# ce2_redraw.net
KiCad netlist of a schematic drawn in EAGLE
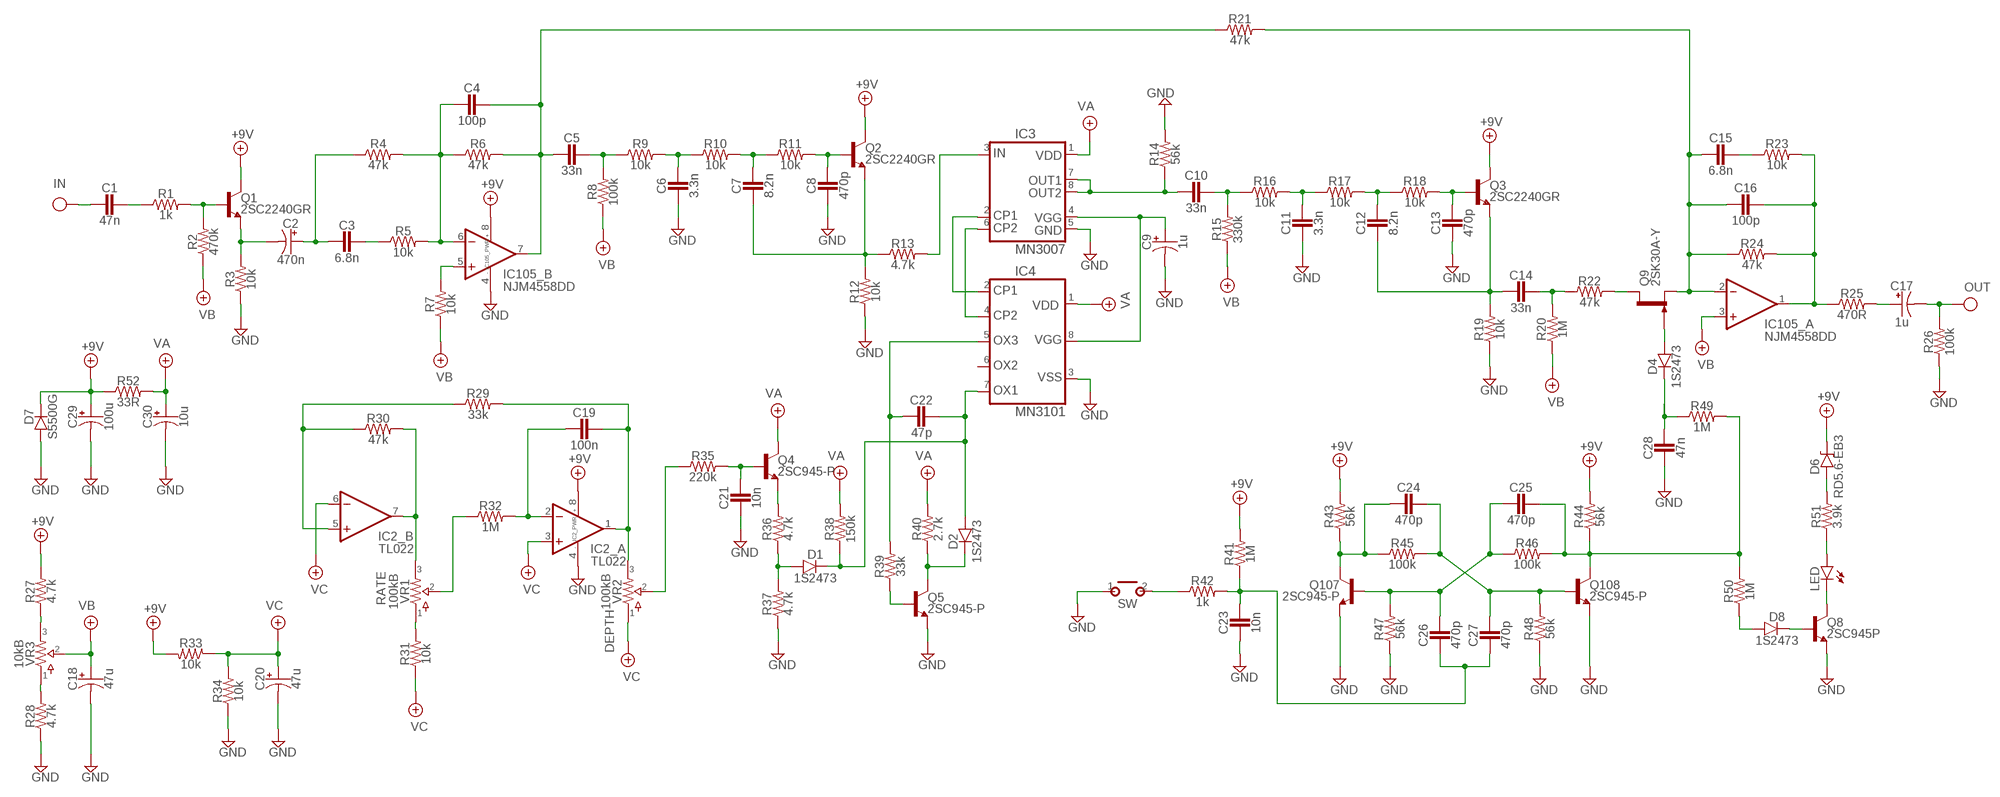
[diagram p0: schematic, sheet 1]

(export (version "E")
  (design (tool "Eeschema 10.0.6"))
  (components
    (comp (ref "C1")
      (value "47n")
      (footprint "eagle-import:BOX_SMALL")
      (libsource (lib "eagle-import") (part "CER/FILMBOX.1"))
    )
    (comp (ref "C2")
      (value "470n")
      (footprint "eagle-import:040_020")
      (libsource (lib "eagle-import") (part "0400"))
    )
    (comp (ref "C3")
      (value "6.8n")
      (footprint "eagle-import:BOX_SMALL")
      (libsource (lib "eagle-import") (part "CER/FILMBOX.1"))
    )
    (comp (ref "C4")
      (value "100p")
      (footprint "eagle-import:BOX_SMALL")
      (libsource (lib "eagle-import") (part "CER/FILMBOX.1"))
    )
    (comp (ref "C5")
      (value "33n")
      (footprint "eagle-import:BOX_SMALL")
      (libsource (lib "eagle-import") (part "CER/FILMBOX.1"))
    )
    (comp (ref "C6")
      (value "3.3n")
      (footprint "eagle-import:BOX_SMALL")
      (libsource (lib "eagle-import") (part "CER/FILMBOX.1"))
    )
    (comp (ref "C7")
      (value "8.2n")
      (footprint "eagle-import:BOX_SMALL")
      (libsource (lib "eagle-import") (part "CER/FILMBOX.1"))
    )
    (comp (ref "C8")
      (value "470p")
      (footprint "eagle-import:BOX_SMALL")
      (libsource (lib "eagle-import") (part "CER/FILMBOX.1"))
    )
    (comp (ref "C9")
      (value "1u")
      (footprint "eagle-import:040_020")
      (libsource (lib "eagle-import") (part "0400"))
    )
    (comp (ref "C10")
      (value "33n")
      (footprint "eagle-import:BOX_SMALL")
      (libsource (lib "eagle-import") (part "CER/FILMBOX.1"))
    )
    (comp (ref "C11")
      (value "3.3n")
      (footprint "eagle-import:BOX_SMALL")
      (libsource (lib "eagle-import") (part "CER/FILMBOX.1"))
    )
    (comp (ref "C12")
      (value "8.2n")
      (footprint "eagle-import:BOX_SMALL")
      (libsource (lib "eagle-import") (part "CER/FILMBOX.1"))
    )
    (comp (ref "C13")
      (value "470p")
      (footprint "eagle-import:BOX_SMALL")
      (libsource (lib "eagle-import") (part "CER/FILMBOX.1"))
    )
    (comp (ref "C14")
      (value "33n")
      (footprint "eagle-import:BOX_SMALL")
      (libsource (lib "eagle-import") (part "CER/FILMBOX.1"))
    )
    (comp (ref "C15")
      (value "6.8n")
      (footprint "eagle-import:BOX_SMALL")
      (libsource (lib "eagle-import") (part "CER/FILMBOX.1"))
    )
    (comp (ref "C16")
      (value "100p")
      (footprint "eagle-import:BOX_SMALL")
      (libsource (lib "eagle-import") (part "CER/FILMBOX.1"))
    )
    (comp (ref "C17")
      (value "1u")
      (footprint "eagle-import:040_020")
      (libsource (lib "eagle-import") (part "0400"))
    )
    (comp (ref "C18")
      (value "47u")
      (footprint "eagle-import:040_020")
      (libsource (lib "eagle-import") (part "0400"))
    )
    (comp (ref "C19")
      (value "100n")
      (footprint "eagle-import:BOX_SMALL")
      (libsource (lib "eagle-import") (part "CER/FILMBOX.1"))
    )
    (comp (ref "C20")
      (value "47u")
      (footprint "eagle-import:040_020")
      (libsource (lib "eagle-import") (part "0400"))
    )
    (comp (ref "C21")
      (value "10n")
      (footprint "eagle-import:BOX_SMALL")
      (libsource (lib "eagle-import") (part "CER/FILMBOX.1"))
    )
    (comp (ref "C22")
      (value "47p")
      (footprint "eagle-import:BOX_SMALL")
      (libsource (lib "eagle-import") (part "CER/FILMBOX.1"))
    )
    (comp (ref "C23")
      (value "10n")
      (footprint "eagle-import:BOX_SMALL")
      (libsource (lib "eagle-import") (part "CER/FILMBOX.1"))
    )
    (comp (ref "C24")
      (value "470p")
      (footprint "eagle-import:BOX_SMALL")
      (libsource (lib "eagle-import") (part "CER/FILMBOX.1"))
    )
    (comp (ref "C25")
      (value "470p")
      (footprint "eagle-import:BOX_SMALL")
      (libsource (lib "eagle-import") (part "CER/FILMBOX.1"))
    )
    (comp (ref "C26")
      (value "470p")
      (footprint "eagle-import:BOX_SMALL")
      (libsource (lib "eagle-import") (part "CER/FILMBOX.1"))
    )
    (comp (ref "C27")
      (value "470p")
      (footprint "eagle-import:BOX_SMALL")
      (libsource (lib "eagle-import") (part "CER/FILMBOX.1"))
    )
    (comp (ref "C28")
      (value "47n")
      (footprint "eagle-import:BOX_SMALL")
      (libsource (lib "eagle-import") (part "CER/FILMBOX.1"))
    )
    (comp (ref "C29")
      (value "100u")
      (footprint "eagle-import:040_020")
      (libsource (lib "eagle-import") (part "0400"))
    )
    (comp (ref "C30")
      (value "10u")
      (footprint "eagle-import:040_020")
      (libsource (lib "eagle-import") (part "0400"))
    )
    (comp (ref "D1")
      (value "1S2473")
      (footprint "eagle-import:DO35-2")
      (libsource (lib "eagle-import") (part "DO35.2"))
    )
    (comp (ref "D2")
      (value "1S2473")
      (footprint "eagle-import:DO35-2")
      (libsource (lib "eagle-import") (part "DO35.2"))
    )
    (comp (ref "D4")
      (value "1S2473")
      (footprint "eagle-import:DO35-2")
      (libsource (lib "eagle-import") (part "DO35.2"))
    )
    (comp (ref "D6")
      (value "RD5.6-EB3")
      (footprint "eagle-import:DO41-1")
      (libsource (lib "eagle-import") (part "ZENER.1"))
    )
    (comp (ref "D7")
      (value "S5500G")
      (footprint "eagle-import:DO35-2")
      (libsource (lib "eagle-import") (part "DO35.2"))
    )
    (comp (ref "D8")
      (value "1S2473")
      (footprint "eagle-import:DO35-2")
      (libsource (lib "eagle-import") (part "DO35.2"))
    )
    (comp (ref "IC2")
      (value "TL022")
      (footprint "eagle-import:DIL0")
      (libsource (lib "eagle-import") (part "DUALTH"))
    )
    (comp (ref "IC3")
      (value "MN3007")
      (footprint "eagle-import:DIL0")
      (libsource (lib "eagle-import") (part "BL3208"))
    )
    (comp (ref "IC4")
      (value "MN3101")
      (footprint "eagle-import:DIL8")
      (libsource (lib "eagle-import") (part "CLOCK"))
    )
    (comp (ref "IC105")
      (value "NJM4558DD")
      (footprint "eagle-import:DIL0")
      (libsource (lib "eagle-import") (part "DUALTH"))
    )
    (comp (ref "LED")
      (value "LED")
      (footprint "eagle-import:3MM_D")
      (libsource (lib "eagle-import") (part "LED"))
    )
    (comp (ref "Q1")
      (value "2SC2240GR")
      (footprint "eagle-import:TO92-")
      (libsource (lib "eagle-import") (part "2SC828A"))
    )
    (comp (ref "Q2")
      (value "2SC2240GR")
      (footprint "eagle-import:TO92-")
      (libsource (lib "eagle-import") (part "2SC828A"))
    )
    (comp (ref "Q3")
      (value "2SC2240GR")
      (footprint "eagle-import:TO92-")
      (libsource (lib "eagle-import") (part "2SC828A"))
    )
    (comp (ref "Q4")
      (value "2SC945-P")
      (footprint "eagle-import:TO92-")
      (libsource (lib "eagle-import") (part "2SC828A"))
    )
    (comp (ref "Q5")
      (value "2SC945-P")
      (footprint "eagle-import:TO92-")
      (libsource (lib "eagle-import") (part "2SC828A"))
    )
    (comp (ref "Q8")
      (value "2SC945P")
      (footprint "eagle-import:TO92-")
      (libsource (lib "eagle-import") (part "2SC828A"))
    )
    (comp (ref "Q9")
      (value "2SK30A-Y")
      (footprint "eagle-import:TO92-")
      (libsource (lib "eagle-import") (part "2N5457"))
    )
    (comp (ref "Q107")
      (value "2SC945-P")
      (footprint "eagle-import:TO92-")
      (libsource (lib "eagle-import") (part "2SC828A"))
    )
    (comp (ref "Q108")
      (value "2SC945-P")
      (footprint "eagle-import:TO92-")
      (libsource (lib "eagle-import") (part "2SC828A"))
    )
    (comp (ref "R1")
      (value "1k")
      (footprint "eagle-import:R0207_3")
      (libsource (lib "eagle-import") (part "R_.3B"))
    )
    (comp (ref "R2")
      (value "470k")
      (footprint "eagle-import:R0207_3")
      (libsource (lib "eagle-import") (part "R_.3B"))
    )
    (comp (ref "R3")
      (value "10k")
      (footprint "eagle-import:R0207_3")
      (libsource (lib "eagle-import") (part "R_.3B"))
    )
    (comp (ref "R4")
      (value "47k")
      (footprint "eagle-import:R0207_3")
      (libsource (lib "eagle-import") (part "R_.3B"))
    )
    (comp (ref "R5")
      (value "10k")
      (footprint "eagle-import:R0207_3")
      (libsource (lib "eagle-import") (part "R_.3B"))
    )
    (comp (ref "R6")
      (value "47k")
      (footprint "eagle-import:R0207_3")
      (libsource (lib "eagle-import") (part "R_.3B"))
    )
    (comp (ref "R7")
      (value "10k")
      (footprint "eagle-import:R0207_3")
      (libsource (lib "eagle-import") (part "R_.3B"))
    )
    (comp (ref "R8")
      (value "100k")
      (footprint "eagle-import:R0207_3")
      (libsource (lib "eagle-import") (part "R_.3B"))
    )
    (comp (ref "R9")
      (value "10k")
      (footprint "eagle-import:R0207_3")
      (libsource (lib "eagle-import") (part "R_.3B"))
    )
    (comp (ref "R10")
      (value "10k")
      (footprint "eagle-import:R0207_3")
      (libsource (lib "eagle-import") (part "R_.3B"))
    )
    (comp (ref "R11")
      (value "10k")
      (footprint "eagle-import:R0207_3")
      (libsource (lib "eagle-import") (part "R_.3B"))
    )
    (comp (ref "R12")
      (value "10k")
      (footprint "eagle-import:R0207_3")
      (libsource (lib "eagle-import") (part "R_.3B"))
    )
    (comp (ref "R13")
      (value "4.7k")
      (footprint "eagle-import:R0207_3")
      (libsource (lib "eagle-import") (part "R_.3B"))
    )
    (comp (ref "R14")
      (value "56k")
      (footprint "eagle-import:R0207_3")
      (libsource (lib "eagle-import") (part "R_.3B"))
    )
    (comp (ref "R15")
      (value "330k")
      (footprint "eagle-import:R0207_3")
      (libsource (lib "eagle-import") (part "R_.3B"))
    )
    (comp (ref "R16")
      (value "10k")
      (footprint "eagle-import:R0207_3")
      (libsource (lib "eagle-import") (part "R_.3B"))
    )
    (comp (ref "R17")
      (value "10k")
      (footprint "eagle-import:R0207_3")
      (libsource (lib "eagle-import") (part "R_.3B"))
    )
    (comp (ref "R18")
      (value "10k")
      (footprint "eagle-import:R0207_3")
      (libsource (lib "eagle-import") (part "R_.3B"))
    )
    (comp (ref "R19")
      (value "10k")
      (footprint "eagle-import:R0207_3")
      (libsource (lib "eagle-import") (part "R_.3B"))
    )
    (comp (ref "R20")
      (value "1M")
      (footprint "eagle-import:R0207_3")
      (libsource (lib "eagle-import") (part "R_.3B"))
    )
    (comp (ref "R21")
      (value "47k")
      (footprint "eagle-import:R0207_3")
      (libsource (lib "eagle-import") (part "R_.3B"))
    )
    (comp (ref "R22")
      (value "47k")
      (footprint "eagle-import:R0207_3")
      (libsource (lib "eagle-import") (part "R_.3B"))
    )
    (comp (ref "R23")
      (value "10k")
      (footprint "eagle-import:R0207_3")
      (libsource (lib "eagle-import") (part "R_.3B"))
    )
    (comp (ref "R24")
      (value "47k")
      (footprint "eagle-import:R0207_3")
      (libsource (lib "eagle-import") (part "R_.3B"))
    )
    (comp (ref "R25")
      (value "470R")
      (footprint "eagle-import:R0207_3")
      (libsource (lib "eagle-import") (part "R_.3B"))
    )
    (comp (ref "R26")
      (value "100k")
      (footprint "eagle-import:R0207_3")
      (libsource (lib "eagle-import") (part "R_.3B"))
    )
    (comp (ref "R27")
      (value "4.7k")
      (footprint "eagle-import:R0207_3")
      (libsource (lib "eagle-import") (part "R_.3B"))
    )
    (comp (ref "R28")
      (value "4.7k")
      (footprint "eagle-import:R0207_3")
      (libsource (lib "eagle-import") (part "R_.3B"))
    )
    (comp (ref "R29")
      (value "33k")
      (footprint "eagle-import:R0207_3")
      (libsource (lib "eagle-import") (part "R_.3B"))
    )
    (comp (ref "R30")
      (value "47k")
      (footprint "eagle-import:R0207_3")
      (libsource (lib "eagle-import") (part "R_.3B"))
    )
    (comp (ref "R31")
      (value "10k")
      (footprint "eagle-import:R0207_3")
      (libsource (lib "eagle-import") (part "R_.3B"))
    )
    (comp (ref "R32")
      (value "1M")
      (footprint "eagle-import:R0207_3")
      (libsource (lib "eagle-import") (part "R_.3B"))
    )
    (comp (ref "R33")
      (value "10k")
      (footprint "eagle-import:R0207_3")
      (libsource (lib "eagle-import") (part "R_.3B"))
    )
    (comp (ref "R34")
      (value "10k")
      (footprint "eagle-import:R0207_3")
      (libsource (lib "eagle-import") (part "R_.3B"))
    )
    (comp (ref "R35")
      (value "220k")
      (footprint "eagle-import:R0207_3")
      (libsource (lib "eagle-import") (part "R_.3B"))
    )
    (comp (ref "R36")
      (value "4.7k")
      (footprint "eagle-import:R0207_3")
      (libsource (lib "eagle-import") (part "R_.3B"))
    )
    (comp (ref "R37")
      (value "4.7k")
      (footprint "eagle-import:R0207_3")
      (libsource (lib "eagle-import") (part "R_.3B"))
    )
    (comp (ref "R38")
      (value "150k")
      (footprint "eagle-import:R0207_3")
      (libsource (lib "eagle-import") (part "R_.3B"))
    )
    (comp (ref "R39")
      (value "33k")
      (footprint "eagle-import:R0207_3")
      (libsource (lib "eagle-import") (part "R_.3B"))
    )
    (comp (ref "R40")
      (value "2.7k")
      (footprint "eagle-import:R0207_3")
      (libsource (lib "eagle-import") (part "R_.3B"))
    )
    (comp (ref "R41")
      (value "1M")
      (footprint "eagle-import:R0207_3")
      (libsource (lib "eagle-import") (part "R_.3B"))
    )
    (comp (ref "R42")
      (value "1k")
      (footprint "eagle-import:R0207_3")
      (libsource (lib "eagle-import") (part "R_.3B"))
    )
    (comp (ref "R43")
      (value "56k")
      (footprint "eagle-import:R0207_3")
      (libsource (lib "eagle-import") (part "R_.3B"))
    )
    (comp (ref "R44")
      (value "56k")
      (footprint "eagle-import:R0207_3")
      (libsource (lib "eagle-import") (part "R_.3B"))
    )
    (comp (ref "R45")
      (value "100k")
      (footprint "eagle-import:R0207_3")
      (libsource (lib "eagle-import") (part "R_.3B"))
    )
    (comp (ref "R46")
      (value "100k")
      (footprint "eagle-import:R0207_3")
      (libsource (lib "eagle-import") (part "R_.3B"))
    )
    (comp (ref "R47")
      (value "56k")
      (footprint "eagle-import:R0207_3")
      (libsource (lib "eagle-import") (part "R_.3B"))
    )
    (comp (ref "R48")
      (value "56k")
      (footprint "eagle-import:R0207_3")
      (libsource (lib "eagle-import") (part "R_.3B"))
    )
    (comp (ref "R49")
      (value "1M")
      (footprint "eagle-import:R0207_3")
      (libsource (lib "eagle-import") (part "R_.3B"))
    )
    (comp (ref "R50")
      (value "1M")
      (footprint "eagle-import:R0207_3")
      (libsource (lib "eagle-import") (part "R_.3B"))
    )
    (comp (ref "R51")
      (value "3.9k")
      (footprint "eagle-import:R0207_3")
      (libsource (lib "eagle-import") (part "R_.3B"))
    )
    (comp (ref "R52")
      (value "33R")
      (footprint "eagle-import:R0207_3")
      (libsource (lib "eagle-import") (part "R_.3B"))
    )
    (comp (ref "SW")
      (value "MOMENTARY")
      (footprint "eagle-import:SPST")
      (libsource (lib "eagle-import") (part "MOMENTARY"))
    )
    (comp (ref "VR1")
      (value "100kB")
      (footprint "eagle-import:16MM")
      (libsource (lib "eagle-import") (part "POTS16MM"))
    )
    (comp (ref "VR2")
      (value "100kB")
      (footprint "eagle-import:16MM")
      (libsource (lib "eagle-import") (part "POTS16MM"))
    )
    (comp (ref "VR3")
      (value "10kB")
      (footprint "eagle-import:16MM")
      (libsource (lib "eagle-import") (part "POTS16MM"))
    )
  )
  (nets
    (net (code "1") (name "+9V") (class "Default")
      (node (ref "C29") (pin "+") (pinfunction "+_+") (pintype "passive"))
      (node (ref "D6") (pin "C") (pinfunction "C_C") (pintype "passive"))
      (node (ref "D7") (pin "C") (pinfunction "C_C") (pintype "passive"))
      (node (ref "IC105") (pin "8") (pinfunction "V+_8") (pintype "power_in"))
      (node (ref "IC2") (pin "8") (pinfunction "V+_8") (pintype "power_in"))
      (node (ref "Q1") (pin "2") (pinfunction "C_2") (pintype "passive"))
      (node (ref "Q2") (pin "2") (pinfunction "C_2") (pintype "passive"))
      (node (ref "Q3") (pin "2") (pinfunction "C_2") (pintype "passive"))
      (node (ref "R27") (pin "2") (pinfunction "2_2") (pintype "passive"))
      (node (ref "R33") (pin "2") (pinfunction "2_2") (pintype "passive"))
      (node (ref "R41") (pin "2") (pinfunction "2_2") (pintype "passive"))
      (node (ref "R43") (pin "2") (pinfunction "2_2") (pintype "passive"))
      (node (ref "R44") (pin "2") (pinfunction "2_2") (pintype "passive"))
      (node (ref "R52") (pin "1") (pinfunction "1_1") (pintype "passive"))
    )
    (net (code "2") (name "GND") (class "Default")
      (node (ref "C11") (pin "2") (pinfunction "2_2") (pintype "passive"))
      (node (ref "C13") (pin "2") (pinfunction "2_2") (pintype "passive"))
      (node (ref "C18") (pin "-") (pinfunction "-_-") (pintype "passive"))
      (node (ref "C20") (pin "-") (pinfunction "-_-") (pintype "passive"))
      (node (ref "C21") (pin "2") (pinfunction "2_2") (pintype "passive"))
      (node (ref "C23") (pin "2") (pinfunction "2_2") (pintype "passive"))
      (node (ref "C28") (pin "2") (pinfunction "2_2") (pintype "passive"))
      (node (ref "C29") (pin "-") (pinfunction "-_-") (pintype "passive"))
      (node (ref "C30") (pin "-") (pinfunction "-_-") (pintype "passive"))
      (node (ref "C6") (pin "2") (pinfunction "2_2") (pintype "passive"))
      (node (ref "C8") (pin "2") (pinfunction "2_2") (pintype "passive"))
      (node (ref "C9") (pin "-") (pinfunction "-_-") (pintype "passive"))
      (node (ref "D7") (pin "A") (pinfunction "A_A") (pintype "passive"))
      (node (ref "IC105") (pin "4") (pinfunction "V-_4") (pintype "power_in"))
      (node (ref "IC2") (pin "4") (pinfunction "V-_4") (pintype "power_in"))
      (node (ref "IC3") (pin "5") (pinfunction "5_5") (pintype "bidirectional"))
      (node (ref "IC4") (pin "3") (pinfunction "P$3_3") (pintype "bidirectional"))
      (node (ref "Q107") (pin "3") (pinfunction "E_3") (pintype "passive"))
      (node (ref "Q108") (pin "3") (pinfunction "E_3") (pintype "passive"))
      (node (ref "Q5") (pin "3") (pinfunction "E_3") (pintype "passive"))
      (node (ref "Q8") (pin "3") (pinfunction "E_3") (pintype "passive"))
      (node (ref "R12") (pin "1") (pinfunction "1_1") (pintype "passive"))
      (node (ref "R14") (pin "2") (pinfunction "2_2") (pintype "passive"))
      (node (ref "R19") (pin "1") (pinfunction "1_1") (pintype "passive"))
      (node (ref "R26") (pin "1") (pinfunction "1_1") (pintype "passive"))
      (node (ref "R28") (pin "1") (pinfunction "1_1") (pintype "passive"))
      (node (ref "R3") (pin "1") (pinfunction "1_1") (pintype "passive"))
      (node (ref "R34") (pin "1") (pinfunction "1_1") (pintype "passive"))
      (node (ref "R37") (pin "1") (pinfunction "1_1") (pintype "passive"))
      (node (ref "R47") (pin "1") (pinfunction "1_1") (pintype "passive"))
      (node (ref "R48") (pin "1") (pinfunction "1_1") (pintype "passive"))
      (node (ref "SW") (pin "1") (pinfunction "P_1") (pintype "passive"))
    )
    (net (code "3") (name "IN") (class "Default")
      (node (ref "C1") (pin "2") (pinfunction "2_2") (pintype "passive"))
    )
    (net (code "4") (name "Net-(C1-Pad1)") (class "Default")
      (node (ref "C1") (pin "1") (pinfunction "1_1") (pintype "passive"))
      (node (ref "R1") (pin "1") (pinfunction "1_1") (pintype "passive"))
    )
    (net (code "5") (name "Net-(C2-Pad+)") (class "Default")
      (node (ref "C2") (pin "+") (pinfunction "+_+") (pintype "passive"))
      (node (ref "C3") (pin "2") (pinfunction "2_2") (pintype "passive"))
      (node (ref "R4") (pin "1") (pinfunction "1_1") (pintype "passive"))
    )
    (net (code "6") (name "Net-(C3-Pad1)") (class "Default")
      (node (ref "C3") (pin "1") (pinfunction "1_1") (pintype "passive"))
      (node (ref "R5") (pin "1") (pinfunction "1_1") (pintype "passive"))
    )
    (net (code "7") (name "Net-(C5-Pad1)") (class "Default")
      (node (ref "C5") (pin "1") (pinfunction "1_1") (pintype "passive"))
      (node (ref "R8") (pin "2") (pinfunction "2_2") (pintype "passive"))
      (node (ref "R9") (pin "1") (pinfunction "1_1") (pintype "passive"))
    )
    (net (code "8") (name "Net-(C6-Pad1)") (class "Default")
      (node (ref "C6") (pin "1") (pinfunction "1_1") (pintype "passive"))
      (node (ref "R10") (pin "1") (pinfunction "1_1") (pintype "passive"))
      (node (ref "R9") (pin "2") (pinfunction "2_2") (pintype "passive"))
    )
    (net (code "9") (name "Net-(C7-Pad1)") (class "Default")
      (node (ref "C7") (pin "1") (pinfunction "1_1") (pintype "passive"))
      (node (ref "R10") (pin "2") (pinfunction "2_2") (pintype "passive"))
      (node (ref "R11") (pin "1") (pinfunction "1_1") (pintype "passive"))
    )
    (net (code "10") (name "Net-(C10-Pad1)") (class "Default")
      (node (ref "C10") (pin "1") (pinfunction "1_1") (pintype "passive"))
      (node (ref "R15") (pin "2") (pinfunction "2_2") (pintype "passive"))
      (node (ref "R16") (pin "1") (pinfunction "1_1") (pintype "passive"))
    )
    (net (code "11") (name "Net-(C10-Pad2)") (class "Default")
      (node (ref "C10") (pin "2") (pinfunction "2_2") (pintype "passive"))
      (node (ref "IC3") (pin "7") (pinfunction "7_7") (pintype "bidirectional"))
      (node (ref "IC3") (pin "8") (pinfunction "8_8") (pintype "bidirectional"))
      (node (ref "R14") (pin "1") (pinfunction "1_1") (pintype "passive"))
    )
    (net (code "12") (name "Net-(C11-Pad1)") (class "Default")
      (node (ref "C11") (pin "1") (pinfunction "1_1") (pintype "passive"))
      (node (ref "R16") (pin "2") (pinfunction "2_2") (pintype "passive"))
      (node (ref "R17") (pin "1") (pinfunction "1_1") (pintype "passive"))
    )
    (net (code "13") (name "Net-(C12-Pad1)") (class "Default")
      (node (ref "C12") (pin "1") (pinfunction "1_1") (pintype "passive"))
      (node (ref "R17") (pin "2") (pinfunction "2_2") (pintype "passive"))
      (node (ref "R18") (pin "1") (pinfunction "1_1") (pintype "passive"))
    )
    (net (code "14") (name "Net-(C14-Pad1)") (class "Default")
      (node (ref "C14") (pin "1") (pinfunction "1_1") (pintype "passive"))
      (node (ref "R20") (pin "2") (pinfunction "2_2") (pintype "passive"))
      (node (ref "R22") (pin "1") (pinfunction "1_1") (pintype "passive"))
    )
    (net (code "15") (name "Net-(C15-Pad1)") (class "Default")
      (node (ref "C15") (pin "1") (pinfunction "1_1") (pintype "passive"))
      (node (ref "R23") (pin "1") (pinfunction "1_1") (pintype "passive"))
    )
    (net (code "16") (name "Net-(C17-Pad+)") (class "Default")
      (node (ref "C17") (pin "+") (pinfunction "+_+") (pintype "passive"))
      (node (ref "R25") (pin "2") (pinfunction "2_2") (pintype "passive"))
    )
    (net (code "17") (name "Net-(C23-Pad1)") (class "Default")
      (node (ref "C23") (pin "1") (pinfunction "1_1") (pintype "passive"))
      (node (ref "C26") (pin "2") (pinfunction "2_2") (pintype "passive"))
      (node (ref "C27") (pin "2") (pinfunction "2_2") (pintype "passive"))
      (node (ref "R41") (pin "1") (pinfunction "1_1") (pintype "passive"))
      (node (ref "R42") (pin "2") (pinfunction "2_2") (pintype "passive"))
    )
    (net (code "18") (name "Net-(C28-Pad1)") (class "Default")
      (node (ref "C28") (pin "1") (pinfunction "1_1") (pintype "passive"))
      (node (ref "D4") (pin "C") (pinfunction "C_C") (pintype "passive"))
      (node (ref "R49") (pin "1") (pinfunction "1_1") (pintype "passive"))
    )
    (net (code "19") (name "Net-(D1-PadA)") (class "Default")
      (node (ref "D1") (pin "A") (pinfunction "A_A") (pintype "passive"))
      (node (ref "R36") (pin "1") (pinfunction "1_1") (pintype "passive"))
      (node (ref "R37") (pin "2") (pinfunction "2_2") (pintype "passive"))
    )
    (net (code "20") (name "Net-(D6-PadA)") (class "Default")
      (node (ref "D6") (pin "A") (pinfunction "A_A") (pintype "passive"))
      (node (ref "R51") (pin "2") (pinfunction "2_2") (pintype "passive"))
    )
    (net (code "21") (name "Net-(D8-PadA)") (class "Default")
      (node (ref "D8") (pin "A") (pinfunction "A_A") (pintype "passive"))
      (node (ref "R50") (pin "1") (pinfunction "1_1") (pintype "passive"))
    )
    (net (code "22") (name "Net-(IC2A--IN)") (class "Default")
      (node (ref "C19") (pin "2") (pinfunction "2_2") (pintype "passive"))
      (node (ref "IC2") (pin "2") (pinfunction "-IN_2") (pintype "input"))
      (node (ref "R32") (pin "2") (pinfunction "2_2") (pintype "passive"))
    )
    (net (code "23") (name "Net-(IC2A-OUT)") (class "Default")
      (node (ref "C19") (pin "1") (pinfunction "1_1") (pintype "passive"))
      (node (ref "IC2") (pin "1") (pinfunction "OUT_1") (pintype "output"))
      (node (ref "R29") (pin "2") (pinfunction "2_2") (pintype "passive"))
      (node (ref "VR2") (pin "3") (pinfunction "3_3") (pintype "passive"))
    )
    (net (code "24") (name "Net-(IC2B-+IN)") (class "Default")
      (node (ref "IC2") (pin "5") (pinfunction "+IN_5") (pintype "input"))
      (node (ref "R29") (pin "1") (pinfunction "1_1") (pintype "passive"))
      (node (ref "R30") (pin "1") (pinfunction "1_1") (pintype "passive"))
    )
    (net (code "25") (name "Net-(IC2B-OUT)") (class "Default")
      (node (ref "IC2") (pin "7") (pinfunction "OUT_7") (pintype "output"))
      (node (ref "R30") (pin "2") (pinfunction "2_2") (pintype "passive"))
      (node (ref "VR1") (pin "3") (pinfunction "3_3") (pintype "passive"))
    )
    (net (code "26") (name "Net-(IC3-Pad3)") (class "Default")
      (node (ref "IC3") (pin "3") (pinfunction "3_3") (pintype "bidirectional"))
      (node (ref "R13") (pin "2") (pinfunction "2_2") (pintype "passive"))
    )
    (net (code "27") (name "Net-(IC4-P$2)") (class "Default")
      (node (ref "IC3") (pin "2") (pinfunction "2_2") (pintype "bidirectional"))
      (node (ref "IC4") (pin "2") (pinfunction "P$2_2") (pintype "bidirectional"))
    )
    (net (code "28") (name "Net-(IC4-P$4)") (class "Default")
      (node (ref "IC3") (pin "6") (pinfunction "6_6") (pintype "bidirectional"))
      (node (ref "IC4") (pin "4") (pinfunction "P$4_4") (pintype "bidirectional"))
    )
    (net (code "29") (name "Net-(IC4-P$5)") (class "Default")
      (node (ref "C22") (pin "2") (pinfunction "2_2") (pintype "passive"))
      (node (ref "IC4") (pin "5") (pinfunction "P$5_5") (pintype "bidirectional"))
      (node (ref "R39") (pin "2") (pinfunction "2_2") (pintype "passive"))
    )
    (net (code "30") (name "Net-(IC4-P$7)") (class "Default")
      (node (ref "C22") (pin "1") (pinfunction "1_1") (pintype "passive"))
      (node (ref "D1") (pin "C") (pinfunction "C_C") (pintype "passive"))
      (node (ref "D2") (pin "A") (pinfunction "A_A") (pintype "passive"))
      (node (ref "IC4") (pin "7") (pinfunction "P$7_7") (pintype "bidirectional"))
      (node (ref "R38") (pin "1") (pinfunction "1_1") (pintype "passive"))
    )
    (net (code "31") (name "Net-(IC4-P$8)") (class "Default")
      (node (ref "C9") (pin "+") (pinfunction "+_+") (pintype "passive"))
      (node (ref "IC3") (pin "4") (pinfunction "4_4") (pintype "bidirectional"))
      (node (ref "IC4") (pin "8") (pinfunction "P$8_8") (pintype "bidirectional"))
    )
    (net (code "32") (name "Net-(IC105A--IN)") (class "Default")
      (node (ref "C15") (pin "2") (pinfunction "2_2") (pintype "passive"))
      (node (ref "C16") (pin "2") (pinfunction "2_2") (pintype "passive"))
      (node (ref "IC105") (pin "2") (pinfunction "-IN_2") (pintype "input"))
      (node (ref "Q9") (pin "2") (pinfunction "S_2") (pintype "passive"))
      (node (ref "R21") (pin "2") (pinfunction "2_2") (pintype "passive"))
      (node (ref "R24") (pin "1") (pinfunction "1_1") (pintype "passive"))
    )
    (net (code "33") (name "Net-(IC105A-OUT)") (class "Default")
      (node (ref "C16") (pin "1") (pinfunction "1_1") (pintype "passive"))
      (node (ref "IC105") (pin "1") (pinfunction "OUT_1") (pintype "output"))
      (node (ref "R23") (pin "2") (pinfunction "2_2") (pintype "passive"))
      (node (ref "R24") (pin "2") (pinfunction "2_2") (pintype "passive"))
      (node (ref "R25") (pin "1") (pinfunction "1_1") (pintype "passive"))
    )
    (net (code "34") (name "Net-(IC105B-+IN)") (class "Default")
      (node (ref "IC105") (pin "5") (pinfunction "+IN_5") (pintype "input"))
      (node (ref "R7") (pin "2") (pinfunction "2_2") (pintype "passive"))
    )
    (net (code "35") (name "Net-(IC105B--IN)") (class "Default")
      (node (ref "C4") (pin "2") (pinfunction "2_2") (pintype "passive"))
      (node (ref "IC105") (pin "6") (pinfunction "-IN_6") (pintype "input"))
      (node (ref "R4") (pin "2") (pinfunction "2_2") (pintype "passive"))
      (node (ref "R5") (pin "2") (pinfunction "2_2") (pintype "passive"))
      (node (ref "R6") (pin "1") (pinfunction "1_1") (pintype "passive"))
    )
    (net (code "36") (name "Net-(IC105B-OUT)") (class "Default")
      (node (ref "C4") (pin "1") (pinfunction "1_1") (pintype "passive"))
      (node (ref "C5") (pin "2") (pinfunction "2_2") (pintype "passive"))
      (node (ref "IC105") (pin "7") (pinfunction "OUT_7") (pintype "output"))
      (node (ref "R21") (pin "1") (pinfunction "1_1") (pintype "passive"))
      (node (ref "R6") (pin "2") (pinfunction "2_2") (pintype "passive"))
    )
    (net (code "37") (name "Net-(LED-A)") (class "Default")
      (node (ref "LED") (pin "ANODE") (pinfunction "A_ANODE") (pintype "passive"))
      (node (ref "R51") (pin "1") (pinfunction "1_1") (pintype "passive"))
    )
    (net (code "38") (name "Net-(LED-C)") (class "Default")
      (node (ref "LED") (pin "P$1") (pinfunction "C_P$1") (pintype "passive"))
      (node (ref "Q8") (pin "2") (pinfunction "C_2") (pintype "passive"))
    )
    (net (code "39") (name "Net-(Q1-B)") (class "Default")
      (node (ref "Q1") (pin "1") (pinfunction "B_1") (pintype "passive"))
      (node (ref "R1") (pin "2") (pinfunction "2_2") (pintype "passive"))
      (node (ref "R2") (pin "2") (pinfunction "2_2") (pintype "passive"))
    )
    (net (code "40") (name "Net-(Q1-E)") (class "Default")
      (node (ref "C2") (pin "-") (pinfunction "-_-") (pintype "passive"))
      (node (ref "Q1") (pin "3") (pinfunction "E_3") (pintype "passive"))
      (node (ref "R3") (pin "2") (pinfunction "2_2") (pintype "passive"))
    )
    (net (code "41") (name "Net-(Q2-B)") (class "Default")
      (node (ref "C8") (pin "1") (pinfunction "1_1") (pintype "passive"))
      (node (ref "Q2") (pin "1") (pinfunction "B_1") (pintype "passive"))
      (node (ref "R11") (pin "2") (pinfunction "2_2") (pintype "passive"))
    )
    (net (code "42") (name "Net-(Q2-E)") (class "Default")
      (node (ref "C7") (pin "2") (pinfunction "2_2") (pintype "passive"))
      (node (ref "Q2") (pin "3") (pinfunction "E_3") (pintype "passive"))
      (node (ref "R12") (pin "2") (pinfunction "2_2") (pintype "passive"))
      (node (ref "R13") (pin "1") (pinfunction "1_1") (pintype "passive"))
    )
    (net (code "43") (name "Net-(Q3-B)") (class "Default")
      (node (ref "C13") (pin "1") (pinfunction "1_1") (pintype "passive"))
      (node (ref "Q3") (pin "1") (pinfunction "B_1") (pintype "passive"))
      (node (ref "R18") (pin "2") (pinfunction "2_2") (pintype "passive"))
    )
    (net (code "44") (name "Net-(Q3-E)") (class "Default")
      (node (ref "C12") (pin "2") (pinfunction "2_2") (pintype "passive"))
      (node (ref "C14") (pin "2") (pinfunction "2_2") (pintype "passive"))
      (node (ref "Q3") (pin "3") (pinfunction "E_3") (pintype "passive"))
      (node (ref "R19") (pin "2") (pinfunction "2_2") (pintype "passive"))
    )
    (net (code "45") (name "Net-(Q4-B)") (class "Default")
      (node (ref "C21") (pin "1") (pinfunction "1_1") (pintype "passive"))
      (node (ref "Q4") (pin "1") (pinfunction "B_1") (pintype "passive"))
      (node (ref "R35") (pin "2") (pinfunction "2_2") (pintype "passive"))
    )
    (net (code "46") (name "Net-(Q4-E)") (class "Default")
      (node (ref "Q4") (pin "3") (pinfunction "E_3") (pintype "passive"))
      (node (ref "R36") (pin "2") (pinfunction "2_2") (pintype "passive"))
    )
    (net (code "47") (name "Net-(Q5-B)") (class "Default")
      (node (ref "Q5") (pin "1") (pinfunction "B_1") (pintype "passive"))
      (node (ref "R39") (pin "1") (pinfunction "1_1") (pintype "passive"))
    )
    (net (code "48") (name "Net-(Q5-C)") (class "Default")
      (node (ref "D2") (pin "C") (pinfunction "C_C") (pintype "passive"))
      (node (ref "Q5") (pin "2") (pinfunction "C_2") (pintype "passive"))
      (node (ref "R40") (pin "1") (pinfunction "1_1") (pintype "passive"))
    )
    (net (code "49") (name "Net-(Q8-B)") (class "Default")
      (node (ref "D8") (pin "C") (pinfunction "C_C") (pintype "passive"))
      (node (ref "Q8") (pin "1") (pinfunction "B_1") (pintype "passive"))
    )
    (net (code "50") (name "Net-(Q9-D)") (class "Default")
      (node (ref "Q9") (pin "3") (pinfunction "D_3") (pintype "passive"))
      (node (ref "R22") (pin "2") (pinfunction "2_2") (pintype "passive"))
    )
    (net (code "51") (name "Net-(Q9-G)") (class "Default")
      (node (ref "D4") (pin "A") (pinfunction "A_A") (pintype "passive"))
      (node (ref "Q9") (pin "1") (pinfunction "G_1") (pintype "passive"))
    )
    (net (code "52") (name "Net-(Q107-B)") (class "Default")
      (node (ref "C25") (pin "2") (pinfunction "2_2") (pintype "passive"))
      (node (ref "C26") (pin "1") (pinfunction "1_1") (pintype "passive"))
      (node (ref "Q107") (pin "1") (pinfunction "B_1") (pintype "passive"))
      (node (ref "R46") (pin "1") (pinfunction "1_1") (pintype "passive"))
      (node (ref "R47") (pin "2") (pinfunction "2_2") (pintype "passive"))
    )
    (net (code "53") (name "Net-(Q107-C)") (class "Default")
      (node (ref "C24") (pin "2") (pinfunction "2_2") (pintype "passive"))
      (node (ref "Q107") (pin "2") (pinfunction "C_2") (pintype "passive"))
      (node (ref "R43") (pin "1") (pinfunction "1_1") (pintype "passive"))
      (node (ref "R45") (pin "1") (pinfunction "1_1") (pintype "passive"))
    )
    (net (code "54") (name "Net-(Q108-B)") (class "Default")
      (node (ref "C24") (pin "1") (pinfunction "1_1") (pintype "passive"))
      (node (ref "C27") (pin "1") (pinfunction "1_1") (pintype "passive"))
      (node (ref "Q108") (pin "1") (pinfunction "B_1") (pintype "passive"))
      (node (ref "R45") (pin "2") (pinfunction "2_2") (pintype "passive"))
      (node (ref "R48") (pin "2") (pinfunction "2_2") (pintype "passive"))
    )
    (net (code "55") (name "Net-(Q108-C)") (class "Default")
      (node (ref "C25") (pin "1") (pinfunction "1_1") (pintype "passive"))
      (node (ref "Q108") (pin "2") (pinfunction "C_2") (pintype "passive"))
      (node (ref "R44") (pin "1") (pinfunction "1_1") (pintype "passive"))
      (node (ref "R46") (pin "2") (pinfunction "2_2") (pintype "passive"))
      (node (ref "R49") (pin "2") (pinfunction "2_2") (pintype "passive"))
      (node (ref "R50") (pin "2") (pinfunction "2_2") (pintype "passive"))
    )
    (net (code "56") (name "Net-(R27-Pad1)") (class "Default")
      (node (ref "R27") (pin "1") (pinfunction "1_1") (pintype "passive"))
      (node (ref "VR3") (pin "3") (pinfunction "3_3") (pintype "passive"))
    )
    (net (code "57") (name "Net-(R28-Pad2)") (class "Default")
      (node (ref "R28") (pin "2") (pinfunction "2_2") (pintype "passive"))
      (node (ref "VR3") (pin "1") (pinfunction "1_1") (pintype "passive"))
    )
    (net (code "58") (name "Net-(R31-Pad2)") (class "Default")
      (node (ref "R31") (pin "2") (pinfunction "2_2") (pintype "passive"))
      (node (ref "VR1") (pin "1") (pinfunction "1_1") (pintype "passive"))
    )
    (net (code "59") (name "Net-(R32-Pad1)") (class "Default")
      (node (ref "R32") (pin "1") (pinfunction "1_1") (pintype "passive"))
      (node (ref "VR1") (pin "2") (pinfunction "2_2") (pintype "passive"))
    )
    (net (code "60") (name "Net-(R35-Pad1)") (class "Default")
      (node (ref "R35") (pin "1") (pinfunction "1_1") (pintype "passive"))
      (node (ref "VR2") (pin "2") (pinfunction "2_2") (pintype "passive"))
    )
    (net (code "61") (name "Net-(SW-S)") (class "Default")
      (node (ref "R42") (pin "1") (pinfunction "1_1") (pintype "passive"))
      (node (ref "SW") (pin "2") (pinfunction "S_2") (pintype "passive"))
    )
    (net (code "62") (name "OUT") (class "Default")
      (node (ref "C17") (pin "-") (pinfunction "-_-") (pintype "passive"))
      (node (ref "R26") (pin "2") (pinfunction "2_2") (pintype "passive"))
    )
    (net (code "63") (name "VA") (class "Default")
      (node (ref "C30") (pin "+") (pinfunction "+_+") (pintype "passive"))
      (node (ref "IC3") (pin "1") (pinfunction "1_1") (pintype "bidirectional"))
      (node (ref "IC4") (pin "1") (pinfunction "P$1_1") (pintype "bidirectional"))
      (node (ref "Q4") (pin "2") (pinfunction "C_2") (pintype "passive"))
      (node (ref "R38") (pin "2") (pinfunction "2_2") (pintype "passive"))
      (node (ref "R40") (pin "2") (pinfunction "2_2") (pintype "passive"))
      (node (ref "R52") (pin "2") (pinfunction "2_2") (pintype "passive"))
    )
    (net (code "64") (name "VB") (class "Default")
      (node (ref "C18") (pin "+") (pinfunction "+_+") (pintype "passive"))
      (node (ref "IC105") (pin "3") (pinfunction "+IN_3") (pintype "input"))
      (node (ref "R15") (pin "1") (pinfunction "1_1") (pintype "passive"))
      (node (ref "R2") (pin "1") (pinfunction "1_1") (pintype "passive"))
      (node (ref "R20") (pin "1") (pinfunction "1_1") (pintype "passive"))
      (node (ref "R7") (pin "1") (pinfunction "1_1") (pintype "passive"))
      (node (ref "R8") (pin "1") (pinfunction "1_1") (pintype "passive"))
      (node (ref "VR3") (pin "2") (pinfunction "2_2") (pintype "passive"))
    )
    (net (code "65") (name "VC") (class "Default")
      (node (ref "C20") (pin "+") (pinfunction "+_+") (pintype "passive"))
      (node (ref "IC2") (pin "3") (pinfunction "+IN_3") (pintype "input"))
      (node (ref "IC2") (pin "6") (pinfunction "-IN_6") (pintype "input"))
      (node (ref "R31") (pin "1") (pinfunction "1_1") (pintype "passive"))
      (node (ref "R33") (pin "1") (pinfunction "1_1") (pintype "passive"))
      (node (ref "R34") (pin "2") (pinfunction "2_2") (pintype "passive"))
      (node (ref "VR2") (pin "1") (pinfunction "1_1") (pintype "passive"))
    )
    (net (code "66") (name "unconnected-(IC4-P$6-Pad6)") (class "Default")
      (node (ref "IC4") (pin "6") (pinfunction "P$6_6") (pintype "bidirectional"))
    )
  )
)
